# source_eagle.net
KiCad netlist of a schematic drawn in EAGLE
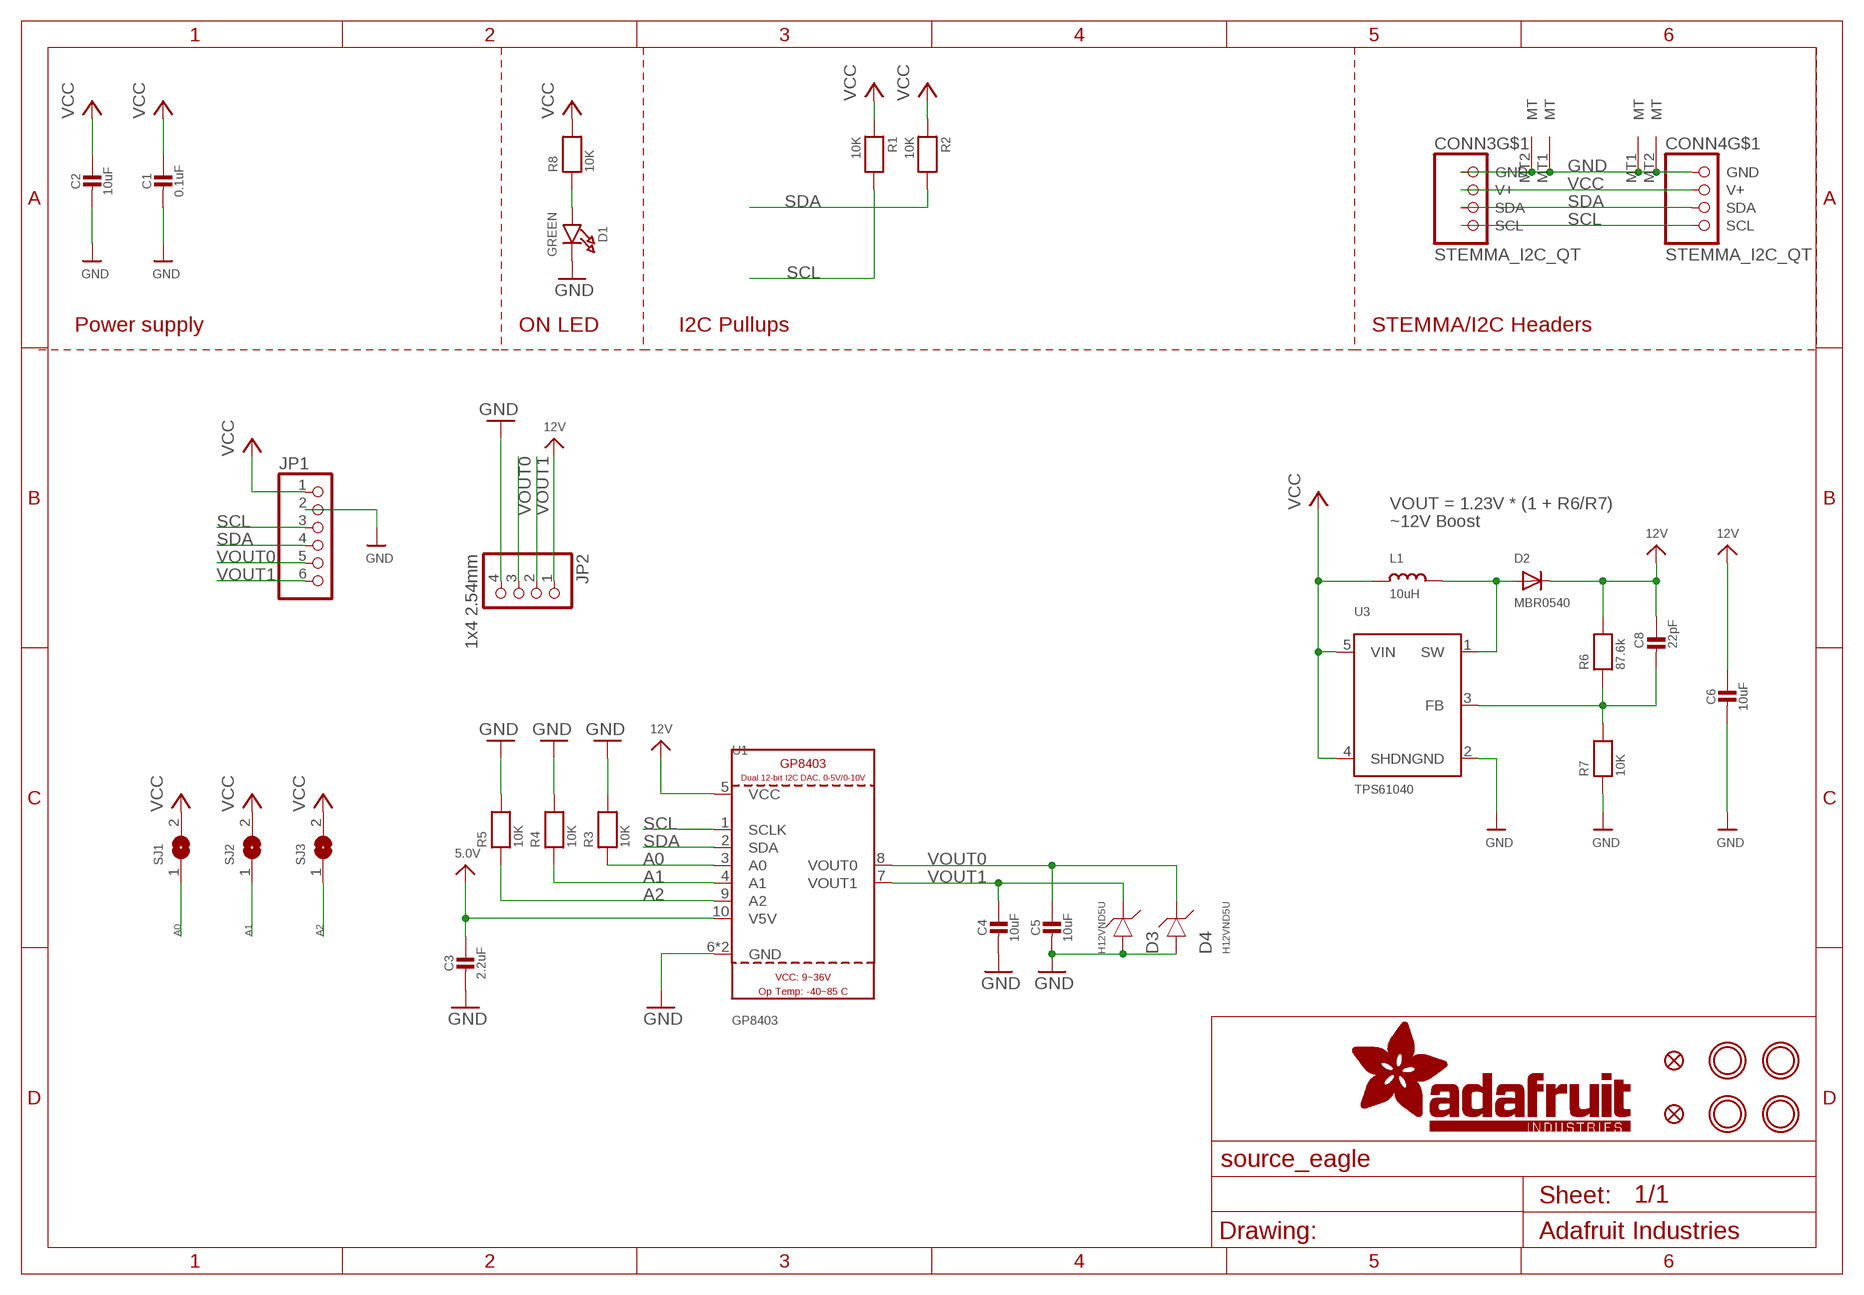
[diagram p0: schematic, sheet 1]

(export (version "E")
  (design (tool "Eeschema 10.0.6"))
  (components
    (comp (ref "C1")
      (value "0.1uF")
      (footprint "eagle-import:0603-NO")
      (libsource (lib "eagle-import") (part "CAP_CERAMIC0603_NO"))
    )
    (comp (ref "C2")
      (value "10uF")
      (footprint "eagle-import:0805-NO")
      (libsource (lib "eagle-import") (part "CAP_CERAMIC0805-NOOUTLINE"))
    )
    (comp (ref "C3")
      (value "2.2uF")
      (footprint "eagle-import:0603-NO")
      (libsource (lib "eagle-import") (part "CAP_CERAMIC0603_NO"))
    )
    (comp (ref "C4")
      (value "10uF")
      (footprint "eagle-import:0805-NO")
      (libsource (lib "eagle-import") (part "CAP_CERAMIC0805-NOOUTLINE"))
    )
    (comp (ref "C5")
      (value "10uF")
      (footprint "eagle-import:0805-NO")
      (libsource (lib "eagle-import") (part "CAP_CERAMIC0805-NOOUTLINE"))
    )
    (comp (ref "C6")
      (value "10uF")
      (footprint "eagle-import:0805-NO")
      (libsource (lib "eagle-import") (part "CAP_CERAMIC0805-NOOUTLINE"))
    )
    (comp (ref "C8")
      (value "22pF")
      (footprint "eagle-import:0603-NO")
      (libsource (lib "eagle-import") (part "CAP_CERAMIC0603_NO"))
    )
    (comp (ref "CONN3")
      (value "STEMMA_I2C_QT")
      (footprint "eagle-import:JST_SH4")
      (libsource (lib "eagle-import") (part "STEMMA_I2C_QT"))
    )
    (comp (ref "CONN4")
      (value "STEMMA_I2C_QT")
      (footprint "eagle-import:JST_SH4")
      (libsource (lib "eagle-import") (part "STEMMA_I2C_QT"))
    )
    (comp (ref "D1")
      (value "GREEN")
      (footprint "eagle-import:CHIPLED_0603_NOOUTLINE")
      (libsource (lib "eagle-import") (part "LED0603_NOOUTLINE"))
    )
    (comp (ref "D2")
      (value "MBR0540")
      (footprint "eagle-import:SOD-123FL")
      (libsource (lib "eagle-import") (part "DIODE_MINISOD123"))
    )
    (comp (ref "D3")
      (value "H12VND5U")
      (footprint "eagle-import:SOD-523")
      (libsource (lib "eagle-import") (part "TVS_SOD523"))
    )
    (comp (ref "D4")
      (value "H12VND5U")
      (footprint "eagle-import:SOD-523")
      (libsource (lib "eagle-import") (part "TVS_SOD523"))
    )
    (comp (ref "FID3")
      (value "FIDUCIAL_0.5MM")
      (footprint "eagle-import:FIDUCIAL_0.5MM")
      (libsource (lib "eagle-import") (part "FIDUCIAL_0.5MM"))
    )
    (comp (ref "FID4")
      (value "FIDUCIAL_0.5MM")
      (footprint "eagle-import:FIDUCIAL_0.5MM")
      (libsource (lib "eagle-import") (part "FIDUCIAL_0.5MM"))
    )
    (comp (ref "JP1")
      (value "HEADER-1X670MIL")
      (footprint "eagle-import:1X06_ROUND_70")
      (libsource (lib "eagle-import") (part "HEADER-1X670MIL"))
    )
    (comp (ref "JP2")
      (value "1x4 2.54mm")
      (footprint "eagle-import:1X04_2.54MMTERMINAL")
      (libsource (lib "eagle-import") (part "HEADER-1X4_254MMTERM"))
    )
    (comp (ref "L1")
      (value "10uH")
      (footprint "eagle-import:INDUCTOR_1007")
      (libsource (lib "eagle-import") (part "INDUCTOR"))
    )
    (comp (ref "R1")
      (value "10K")
      (footprint "eagle-import:0603-NO")
      (libsource (lib "eagle-import") (part "RESISTOR_0603_NOOUT"))
    )
    (comp (ref "R2")
      (value "10K")
      (footprint "eagle-import:0603-NO")
      (libsource (lib "eagle-import") (part "RESISTOR_0603_NOOUT"))
    )
    (comp (ref "R3")
      (value "10K")
      (footprint "eagle-import:0603-NO")
      (libsource (lib "eagle-import") (part "RESISTOR_0603_NOOUT"))
    )
    (comp (ref "R4")
      (value "10K")
      (footprint "eagle-import:0603-NO")
      (libsource (lib "eagle-import") (part "RESISTOR_0603_NOOUT"))
    )
    (comp (ref "R5")
      (value "10K")
      (footprint "eagle-import:0603-NO")
      (libsource (lib "eagle-import") (part "RESISTOR_0603_NOOUT"))
    )
    (comp (ref "R6")
      (value "87.6k")
      (footprint "eagle-import:0603-NO")
      (libsource (lib "eagle-import") (part "RESISTOR_0603_NOOUT"))
    )
    (comp (ref "R7")
      (value "10K")
      (footprint "eagle-import:0603-NO")
      (libsource (lib "eagle-import") (part "RESISTOR_0603_NOOUT"))
    )
    (comp (ref "R8")
      (value "10K")
      (footprint "eagle-import:0603-NO")
      (libsource (lib "eagle-import") (part "RESISTOR_0603_NOOUT"))
    )
    (comp (ref "SJ1")
      (value "SOLDERJUMPER")
      (footprint "eagle-import:SOLDERJUMPER_ARROW_NOPASTE")
      (libsource (lib "eagle-import") (part "SOLDERJUMPER"))
    )
    (comp (ref "SJ2")
      (value "SOLDERJUMPER")
      (footprint "eagle-import:SOLDERJUMPER_ARROW_NOPASTE")
      (libsource (lib "eagle-import") (part "SOLDERJUMPER"))
    )
    (comp (ref "SJ3")
      (value "SOLDERJUMPER")
      (footprint "eagle-import:SOLDERJUMPER_ARROW_NOPASTE")
      (libsource (lib "eagle-import") (part "SOLDERJUMPER"))
    )
    (comp (ref "U$1")
      (value "MOUNTINGHOLE2.5")
      (footprint "eagle-import:MOUNTINGHOLE_2.5_PLATED")
      (libsource (lib "eagle-import") (part "MOUNTINGHOLE2.5"))
    )
    (comp (ref "U$17")
      (value "MOUNTINGHOLE2.5")
      (footprint "eagle-import:MOUNTINGHOLE_2.5_PLATED")
      (libsource (lib "eagle-import") (part "MOUNTINGHOLE2.5"))
    )
    (comp (ref "U$19")
      (value "MOUNTINGHOLE2.5")
      (footprint "eagle-import:MOUNTINGHOLE_2.5_PLATED")
      (libsource (lib "eagle-import") (part "MOUNTINGHOLE2.5"))
    )
    (comp (ref "U$21")
      (value "MOUNTINGHOLE2.5")
      (footprint "eagle-import:MOUNTINGHOLE_2.5_PLATED")
      (libsource (lib "eagle-import") (part "MOUNTINGHOLE2.5"))
    )
    (comp (ref "U1")
      (value "GP8403")
      (footprint "eagle-import:ESSOP10-EP")
      (libsource (lib "eagle-import") (part "DAC_GP8403"))
    )
    (comp (ref "U3")
      (value "TPS61040")
      (footprint "eagle-import:SOT23-5")
      (libsource (lib "eagle-import") (part "VREG_BOOST_5PIN_SOT23"))
    )
  )
  (nets
    (net (code "1") (name "/A0") (class "Default")
      (node (ref "R3") (pin "1") (pinfunction "1_1") (pintype "passive"))
      (node (ref "SJ1") (pin "1") (pinfunction "1_1") (pintype "passive"))
      (node (ref "U1") (pin "3") (pinfunction "A0_3") (pintype "input"))
    )
    (net (code "2") (name "/A1") (class "Default")
      (node (ref "R4") (pin "1") (pinfunction "1_1") (pintype "passive"))
      (node (ref "SJ2") (pin "1") (pinfunction "1_1") (pintype "passive"))
      (node (ref "U1") (pin "4") (pinfunction "A1_4") (pintype "input"))
    )
    (net (code "3") (name "/A2") (class "Default")
      (node (ref "R5") (pin "1") (pinfunction "1_1") (pintype "passive"))
      (node (ref "SJ3") (pin "1") (pinfunction "1_1") (pintype "passive"))
      (node (ref "U1") (pin "9") (pinfunction "A2_9") (pintype "input"))
    )
    (net (code "4") (name "/SCL") (class "Default")
      (node (ref "CONN3") (pin "4") (pinfunction "SCL_4") (pintype "passive"))
      (node (ref "CONN4") (pin "4") (pinfunction "SCL_4") (pintype "passive"))
      (node (ref "JP1") (pin "3") (pinfunction "3_3") (pintype "passive"))
      (node (ref "R1") (pin "2") (pinfunction "2_2") (pintype "passive"))
      (node (ref "U1") (pin "1") (pinfunction "SCLK_1") (pintype "input"))
    )
    (net (code "5") (name "/SDA") (class "Default")
      (node (ref "CONN3") (pin "3") (pinfunction "SDA_3") (pintype "passive"))
      (node (ref "CONN4") (pin "3") (pinfunction "SDA_3") (pintype "passive"))
      (node (ref "JP1") (pin "4") (pinfunction "4_4") (pintype "passive"))
      (node (ref "R2") (pin "2") (pinfunction "2_2") (pintype "passive"))
      (node (ref "U1") (pin "2") (pinfunction "SDA_2") (pintype "bidirectional"))
    )
    (net (code "6") (name "/VOUT0") (class "Default")
      (node (ref "C5") (pin "1") (pinfunction "1_1") (pintype "passive"))
      (node (ref "D4") (pin "K") (pinfunction "C_K") (pintype "bidirectional"))
      (node (ref "JP1") (pin "5") (pinfunction "5_5") (pintype "passive"))
      (node (ref "JP2") (pin "3") (pinfunction "3_3") (pintype "passive"))
      (node (ref "U1") (pin "8") (pinfunction "VOUT0_8") (pintype "output"))
    )
    (net (code "7") (name "/VOUT1") (class "Default")
      (node (ref "C4") (pin "1") (pinfunction "1_1") (pintype "passive"))
      (node (ref "D3") (pin "K") (pinfunction "C_K") (pintype "bidirectional"))
      (node (ref "JP1") (pin "6") (pinfunction "6_6") (pintype "passive"))
      (node (ref "JP2") (pin "2") (pinfunction "2_2") (pintype "passive"))
      (node (ref "U1") (pin "7") (pinfunction "VOUT1_7") (pintype "output"))
    )
    (net (code "8") (name "5.0V") (class "Default")
      (node (ref "C3") (pin "1") (pinfunction "1_1") (pintype "passive"))
      (node (ref "U1") (pin "10") (pinfunction "V5V_10") (pintype "power_in"))
    )
    (net (code "9") (name "12V") (class "Default")
      (node (ref "C6") (pin "1") (pinfunction "1_1") (pintype "passive"))
      (node (ref "C8") (pin "1") (pinfunction "1_1") (pintype "passive"))
      (node (ref "D2") (pin "C") (pinfunction "C_C") (pintype "passive"))
      (node (ref "JP2") (pin "1") (pinfunction "1_1") (pintype "passive"))
      (node (ref "R6") (pin "2") (pinfunction "2_2") (pintype "passive"))
      (node (ref "U1") (pin "5") (pinfunction "VCC_5") (pintype "power_in"))
    )
    (net (code "10") (name "GND") (class "Default")
      (node (ref "C1") (pin "2") (pinfunction "2_2") (pintype "passive"))
      (node (ref "C2") (pin "2") (pinfunction "2_2") (pintype "passive"))
      (node (ref "C3") (pin "2") (pinfunction "2_2") (pintype "passive"))
      (node (ref "C4") (pin "2") (pinfunction "2_2") (pintype "passive"))
      (node (ref "C5") (pin "2") (pinfunction "2_2") (pintype "passive"))
      (node (ref "C6") (pin "2") (pinfunction "2_2") (pintype "passive"))
      (node (ref "CONN3") (pin "1") (pinfunction "GND_1") (pintype "passive"))
      (node (ref "CONN3") (pin "MT1") (pinfunction "MT_MT1") (pintype "bidirectional"))
      (node (ref "CONN3") (pin "MT2") (pinfunction "MT_MT2") (pintype "bidirectional"))
      (node (ref "CONN4") (pin "1") (pinfunction "GND_1") (pintype "passive"))
      (node (ref "CONN4") (pin "MT1") (pinfunction "MT_MT1") (pintype "bidirectional"))
      (node (ref "CONN4") (pin "MT2") (pinfunction "MT_MT2") (pintype "bidirectional"))
      (node (ref "D1") (pin "C") (pinfunction "C_C") (pintype "passive"))
      (node (ref "D3") (pin "A") (pinfunction "A_A") (pintype "bidirectional"))
      (node (ref "D4") (pin "A") (pinfunction "A_A") (pintype "bidirectional"))
      (node (ref "JP1") (pin "2") (pinfunction "2_2") (pintype "passive"))
      (node (ref "JP2") (pin "4") (pinfunction "4_4") (pintype "passive"))
      (node (ref "R3") (pin "2") (pinfunction "2_2") (pintype "passive"))
      (node (ref "R4") (pin "2") (pinfunction "2_2") (pintype "passive"))
      (node (ref "R5") (pin "2") (pinfunction "2_2") (pintype "passive"))
      (node (ref "R7") (pin "1") (pinfunction "1_1") (pintype "passive"))
      (node (ref "U1") (pin "6") (pinfunction "GND_6") (pintype "power_in"))
      (node (ref "U1") (pin "EP") (pinfunction "GND_EP") (pintype "power_in"))
      (node (ref "U3") (pin "2") (pinfunction "GND_2") (pintype "bidirectional"))
    )
    (net (code "11") (name "Net-(D1-PadA)") (class "Default")
      (node (ref "D1") (pin "A") (pinfunction "A_A") (pintype "passive"))
      (node (ref "R8") (pin "1") (pinfunction "1_1") (pintype "passive"))
    )
    (net (code "12") (name "Net-(L1-2)") (class "Default")
      (node (ref "D2") (pin "A") (pinfunction "A_A") (pintype "passive"))
      (node (ref "L1") (pin "P$2") (pinfunction "2_P$2") (pintype "passive"))
      (node (ref "U3") (pin "1") (pinfunction "SW_1") (pintype "bidirectional"))
    )
    (net (code "13") (name "Net-(U3-FB)") (class "Default")
      (node (ref "C8") (pin "2") (pinfunction "2_2") (pintype "passive"))
      (node (ref "R6") (pin "1") (pinfunction "1_1") (pintype "passive"))
      (node (ref "R7") (pin "2") (pinfunction "2_2") (pintype "passive"))
      (node (ref "U3") (pin "3") (pinfunction "FB_3") (pintype "bidirectional"))
    )
    (net (code "14") (name "VCC") (class "Default")
      (node (ref "C1") (pin "1") (pinfunction "1_1") (pintype "passive"))
      (node (ref "C2") (pin "1") (pinfunction "1_1") (pintype "passive"))
      (node (ref "CONN3") (pin "2") (pinfunction "V+_2") (pintype "passive"))
      (node (ref "CONN4") (pin "2") (pinfunction "V+_2") (pintype "passive"))
      (node (ref "JP1") (pin "1") (pinfunction "1_1") (pintype "passive"))
      (node (ref "L1") (pin "P$1") (pinfunction "1_P$1") (pintype "passive"))
      (node (ref "R1") (pin "1") (pinfunction "1_1") (pintype "passive"))
      (node (ref "R2") (pin "1") (pinfunction "1_1") (pintype "passive"))
      (node (ref "R8") (pin "2") (pinfunction "2_2") (pintype "passive"))
      (node (ref "SJ1") (pin "2") (pinfunction "2_2") (pintype "passive"))
      (node (ref "SJ2") (pin "2") (pinfunction "2_2") (pintype "passive"))
      (node (ref "SJ3") (pin "2") (pinfunction "2_2") (pintype "passive"))
      (node (ref "U3") (pin "4") (pinfunction "SHDN_4") (pintype "bidirectional"))
      (node (ref "U3") (pin "5") (pinfunction "VIN_5") (pintype "bidirectional"))
    )
  )
)
